# Adafruit_TRRS_Trinkey.net
KiCad netlist of a schematic drawn in EAGLE
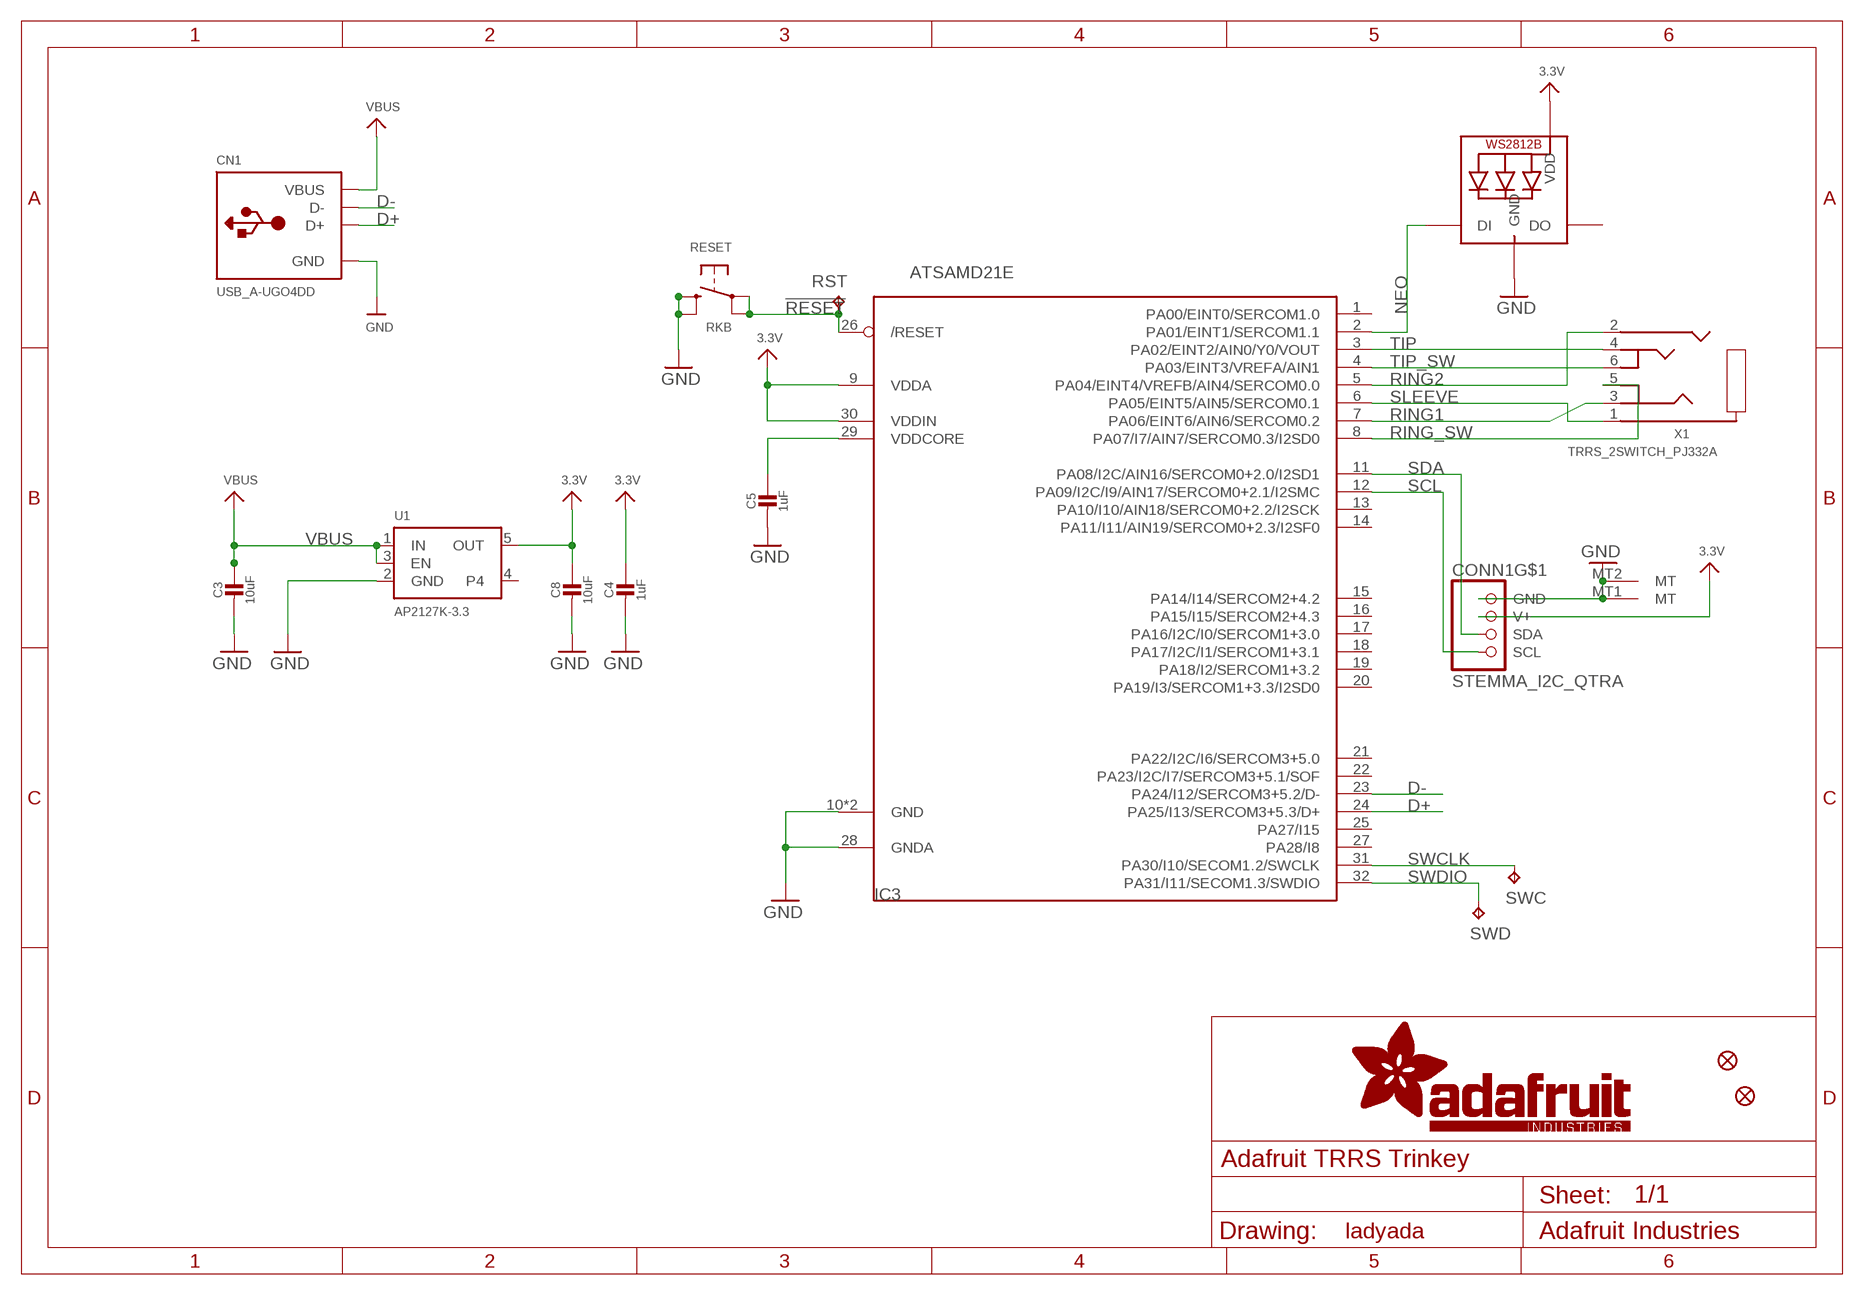
[diagram p0: schematic, sheet 1]

(export (version "E")
  (design (tool "Eeschema 10.0.6"))
  (components
    (comp (ref "C3")
      (value "10uF")
      (footprint "eagle-import:0805-NO")
      (libsource (lib "eagle-import") (part "CAP_CERAMIC0805-NOOUTLINE"))
    )
    (comp (ref "C4")
      (value "1uF")
      (footprint "eagle-import:0603-NO")
      (libsource (lib "eagle-import") (part "CAP_CERAMIC0603_NO"))
    )
    (comp (ref "C5")
      (value "1uF")
      (footprint "eagle-import:0603-NO")
      (libsource (lib "eagle-import") (part "CAP_CERAMIC0603_NO"))
    )
    (comp (ref "C8")
      (value "10uF")
      (footprint "eagle-import:0805-NO")
      (libsource (lib "eagle-import") (part "CAP_CERAMIC0805-NOOUTLINE"))
    )
    (comp (ref "CN1")
      (value "USB_A-UGO4DD")
      (footprint "eagle-import:USB_A-UGO4DD")
      (libsource (lib "eagle-import") (part "USB_TYPEA_UG04DD"))
    )
    (comp (ref "CONN1")
      (value "STEMMA_I2C_QTRA")
      (footprint "eagle-import:JST_SH4_RA")
      (libsource (lib "eagle-import") (part "STEMMA_I2C_QTRA"))
    )
    (comp (ref "FID1")
      (value "FIDUCIAL_0.5MM")
      (footprint "eagle-import:FIDUCIAL_0.5MM")
      (libsource (lib "eagle-import") (part "FIDUCIAL_0.5MM"))
    )
    (comp (ref "FID2")
      (value "FIDUCIAL_0.5MM")
      (footprint "eagle-import:FIDUCIAL_0.5MM")
      (libsource (lib "eagle-import") (part "FIDUCIAL_0.5MM"))
    )
    (comp (ref "IC3")
      (value "ATSAMD21E")
      (footprint "eagle-import:QFN32_5MM")
      (libsource (lib "eagle-import") (part "ATSAMD21E"))
    )
    (comp (ref "LED1")
      (value "WS2812B_SK6805_1515")
      (footprint "eagle-import:SK6805_1515")
      (libsource (lib "eagle-import") (part "WS2812B_SK6805_1515"))
    )
    (comp (ref "RESET")
      (value "RKB")
      (footprint "eagle-import:BTN_RKB2_4.6X2.8")
      (libsource (lib "eagle-import") (part "SWITCH_TACT_SMT_RKB2"))
    )
    (comp (ref "RST")
      (value "TPTP16R")
      (footprint "eagle-import:TP16R")
      (libsource (lib "eagle-import") (part "TPTP16R"))
    )
    (comp (ref "SWC")
      (value "TPTP15R")
      (footprint "eagle-import:TP15R")
      (libsource (lib "eagle-import") (part "TPTP15R"))
    )
    (comp (ref "SWD")
      (value "TPTP16R")
      (footprint "eagle-import:TP16R")
      (libsource (lib "eagle-import") (part "TPTP16R"))
    )
    (comp (ref "U1")
      (value "AP2127K-3.3")
      (footprint "eagle-import:SOT23-5")
      (fields (field (name "JLC_ROTATION") "0"))
      (libsource (lib "eagle-import") (part "VREG_SOT23-5"))
    )
    (comp (ref "X1")
      (value "TRRS_2SWITCH_PJ332A")
      (footprint "eagle-import:PJ-332A")
      (libsource (lib "eagle-import") (part "TRRS_2SWITCH_PJ332A"))
    )
  )
  (nets
    (net (code "1") (name "/D+") (class "Default")
      (node (ref "CN1") (pin "D+") (pinfunction "D+_D+") (pintype "bidirectional"))
      (node (ref "IC3") (pin "24") (pinfunction "PA25/I13/SERCOM3+5.3/D+_24") (pintype "bidirectional"))
    )
    (net (code "2") (name "/D-") (class "Default")
      (node (ref "CN1") (pin "D-") (pinfunction "D-_D-") (pintype "bidirectional"))
      (node (ref "IC3") (pin "23") (pinfunction "PA24/I12/SERCOM3+5.2/D-_23") (pintype "bidirectional"))
    )
    (net (code "3") (name "/NEO") (class "Default")
      (node (ref "IC3") (pin "2") (pinfunction "PA01/EINT1/SERCOM1.1_2") (pintype "bidirectional"))
      (node (ref "LED1") (pin "1") (pinfunction "DI_1") (pintype "input"))
    )
    (net (code "4") (name "/RING1") (class "Default")
      (node (ref "IC3") (pin "7") (pinfunction "PA06/EINT6/AIN6/SERCOM0.2_7") (pintype "bidirectional"))
      (node (ref "X1") (pin "3") (pinfunction "RING2_3") (pintype "passive"))
    )
    (net (code "5") (name "/RING2") (class "Default")
      (node (ref "IC3") (pin "5") (pinfunction "PA04/EINT4/VREFB/AIN4/SERCOM0.0_5") (pintype "bidirectional"))
      (node (ref "X1") (pin "2") (pinfunction "RING1_2") (pintype "passive"))
    )
    (net (code "6") (name "/RING_SW") (class "Default")
      (node (ref "IC3") (pin "8") (pinfunction "PA07/I7/AIN7/SERCOM0.3/I2SD0_8") (pintype "bidirectional"))
      (node (ref "X1") (pin "5") (pinfunction "R2_SW_5") (pintype "passive"))
    )
    (net (code "7") (name "/SCL") (class "Default")
      (node (ref "CONN1") (pin "4") (pinfunction "SCL_4") (pintype "passive"))
      (node (ref "IC3") (pin "12") (pinfunction "PA09/I2C/I9/AIN17/SERCOM0+2.1/I2SMC_12") (pintype "bidirectional"))
    )
    (net (code "8") (name "/SDA") (class "Default")
      (node (ref "CONN1") (pin "3") (pinfunction "SDA_3") (pintype "passive"))
      (node (ref "IC3") (pin "11") (pinfunction "PA08/I2C/AIN16/SERCOM0+2.0/I2SD1_11") (pintype "bidirectional"))
    )
    (net (code "9") (name "/SLEEVE") (class "Default")
      (node (ref "IC3") (pin "6") (pinfunction "PA05/EINT5/AIN5/SERCOM0.1_6") (pintype "bidirectional"))
      (node (ref "X1") (pin "1") (pinfunction "RING_1") (pintype "passive"))
    )
    (net (code "10") (name "/SWCLK") (class "Default")
      (node (ref "IC3") (pin "31") (pinfunction "PA30/I10/SECOM1.2/SWCLK_31") (pintype "bidirectional"))
      (node (ref "SWC") (pin "TP") (pinfunction "TP_TP") (pintype "input"))
    )
    (net (code "11") (name "/SWDIO") (class "Default")
      (node (ref "IC3") (pin "32") (pinfunction "PA31/I11/SECOM1.3/SWDIO_32") (pintype "bidirectional"))
      (node (ref "SWD") (pin "TP") (pinfunction "TP_TP") (pintype "input"))
    )
    (net (code "12") (name "/TIP") (class "Default")
      (node (ref "IC3") (pin "3") (pinfunction "PA02/EINT2/AIN0/Y0/VOUT_3") (pintype "bidirectional"))
      (node (ref "X1") (pin "4") (pinfunction "TIP_4") (pintype "passive"))
    )
    (net (code "13") (name "/TIP_SW") (class "Default")
      (node (ref "IC3") (pin "4") (pinfunction "PA03/EINT3/VREFA/AIN1_4") (pintype "bidirectional"))
      (node (ref "X1") (pin "6") (pinfunction "TIP_SW_6") (pintype "passive"))
    )
    (net (code "14") (name "/~{RESET}") (class "Default")
      (node (ref "IC3") (pin "26") (pinfunction "/RESET_26") (pintype "bidirectional"))
      (node (ref "RESET") (pin "A") (pinfunction "P_A") (pintype "passive"))
      (node (ref "RESET") (pin "A'") (pinfunction "P1_A'") (pintype "passive"))
      (node (ref "RST") (pin "TP") (pinfunction "TP_TP") (pintype "input"))
    )
    (net (code "15") (name "3.3V") (class "Default")
      (node (ref "C4") (pin "1") (pinfunction "1_1") (pintype "passive"))
      (node (ref "C8") (pin "1") (pinfunction "1_1") (pintype "passive"))
      (node (ref "CONN1") (pin "2") (pinfunction "V+_2") (pintype "passive"))
      (node (ref "IC3") (pin "30") (pinfunction "VDDIN_30") (pintype "power_in"))
      (node (ref "IC3") (pin "9") (pinfunction "VDDA_9") (pintype "power_in"))
      (node (ref "LED1") (pin "2") (pinfunction "VDD_2") (pintype "power_in"))
      (node (ref "U1") (pin "5") (pinfunction "OUT_5") (pintype "power_in"))
    )
    (net (code "16") (name "GND") (class "Default")
      (node (ref "C3") (pin "2") (pinfunction "2_2") (pintype "passive"))
      (node (ref "C4") (pin "2") (pinfunction "2_2") (pintype "passive"))
      (node (ref "C5") (pin "2") (pinfunction "2_2") (pintype "passive"))
      (node (ref "C8") (pin "2") (pinfunction "2_2") (pintype "passive"))
      (node (ref "CN1") (pin "GND") (pinfunction "GND_GND") (pintype "power_in"))
      (node (ref "CONN1") (pin "1") (pinfunction "GND_1") (pintype "passive"))
      (node (ref "CONN1") (pin "MT1") (pinfunction "MT_MT1") (pintype "bidirectional"))
      (node (ref "CONN1") (pin "MT2") (pinfunction "MT_MT2") (pintype "bidirectional"))
      (node (ref "IC3") (pin "10") (pinfunction "GND_10") (pintype "power_in"))
      (node (ref "IC3") (pin "28") (pinfunction "GNDA_28") (pintype "power_in"))
      (node (ref "IC3") (pin "33") (pinfunction "GND_33") (pintype "power_in"))
      (node (ref "LED1") (pin "4") (pinfunction "GND_4") (pintype "power_in"))
      (node (ref "RESET") (pin "B") (pinfunction "S_B") (pintype "passive"))
      (node (ref "RESET") (pin "B'") (pinfunction "S1_B'") (pintype "passive"))
      (node (ref "U1") (pin "2") (pinfunction "GND_2") (pintype "power_in"))
    )
    (net (code "17") (name "Net-(IC3-VDDCORE)") (class "Default")
      (node (ref "C5") (pin "1") (pinfunction "1_1") (pintype "passive"))
      (node (ref "IC3") (pin "29") (pinfunction "VDDCORE_29") (pintype "power_in"))
    )
    (net (code "18") (name "VBUS") (class "Default")
      (node (ref "C3") (pin "1") (pinfunction "1_1") (pintype "passive"))
      (node (ref "CN1") (pin "VBUS") (pinfunction "VBUS_VBUS") (pintype "power_in"))
      (node (ref "U1") (pin "1") (pinfunction "IN_1") (pintype "power_in"))
      (node (ref "U1") (pin "3") (pinfunction "EN_3") (pintype "input"))
    )
    (net (code "19") (name "unconnected-(IC3-PA00{slash}EINT0{slash}SERCOM1.0-Pad1)") (class "Default")
      (node (ref "IC3") (pin "1") (pinfunction "PA00/EINT0/SERCOM1.0_1") (pintype "bidirectional"))
    )
    (net (code "20") (name "unconnected-(IC3-PA10{slash}I10{slash}AIN18{slash}SERCOM0+2.2{slash}I2SCK-Pad13)") (class "Default")
      (node (ref "IC3") (pin "13") (pinfunction "PA10/I10/AIN18/SERCOM0+2.2/I2SCK_13") (pintype "bidirectional"))
    )
    (net (code "21") (name "unconnected-(IC3-PA11{slash}I11{slash}AIN19{slash}SERCOM0+2.3{slash}I2SF0-Pad14)") (class "Default")
      (node (ref "IC3") (pin "14") (pinfunction "PA11/I11/AIN19/SERCOM0+2.3/I2SF0_14") (pintype "bidirectional"))
    )
    (net (code "22") (name "unconnected-(IC3-PA14{slash}I14{slash}SERCOM2+4.2-Pad15)") (class "Default")
      (node (ref "IC3") (pin "15") (pinfunction "PA14/I14/SERCOM2+4.2_15") (pintype "bidirectional"))
    )
    (net (code "23") (name "unconnected-(IC3-PA15{slash}I15{slash}SERCOM2+4.3-Pad16)") (class "Default")
      (node (ref "IC3") (pin "16") (pinfunction "PA15/I15/SERCOM2+4.3_16") (pintype "bidirectional"))
    )
    (net (code "24") (name "unconnected-(IC3-PA16{slash}I2C{slash}I0{slash}SERCOM1+3.0-Pad17)") (class "Default")
      (node (ref "IC3") (pin "17") (pinfunction "PA16/I2C/I0/SERCOM1+3.0_17") (pintype "bidirectional"))
    )
    (net (code "25") (name "unconnected-(IC3-PA17{slash}I2C{slash}I1{slash}SERCOM1+3.1-Pad18)") (class "Default")
      (node (ref "IC3") (pin "18") (pinfunction "PA17/I2C/I1/SERCOM1+3.1_18") (pintype "bidirectional"))
    )
    (net (code "26") (name "unconnected-(IC3-PA18{slash}I2{slash}SERCOM1+3.2-Pad19)") (class "Default")
      (node (ref "IC3") (pin "19") (pinfunction "PA18/I2/SERCOM1+3.2_19") (pintype "bidirectional"))
    )
    (net (code "27") (name "unconnected-(IC3-PA19{slash}I3{slash}SERCOM1+3.3{slash}I2SD0-Pad20)") (class "Default")
      (node (ref "IC3") (pin "20") (pinfunction "PA19/I3/SERCOM1+3.3/I2SD0_20") (pintype "bidirectional"))
    )
    (net (code "28") (name "unconnected-(IC3-PA22{slash}I2C{slash}I6{slash}SERCOM3+5.0-Pad21)") (class "Default")
      (node (ref "IC3") (pin "21") (pinfunction "PA22/I2C/I6/SERCOM3+5.0_21") (pintype "bidirectional"))
    )
    (net (code "29") (name "unconnected-(IC3-PA23{slash}I2C{slash}I7{slash}SERCOM3+5.1{slash}SOF-Pad22)") (class "Default")
      (node (ref "IC3") (pin "22") (pinfunction "PA23/I2C/I7/SERCOM3+5.1/SOF_22") (pintype "bidirectional"))
    )
    (net (code "30") (name "unconnected-(IC3-PA27{slash}I15-Pad25)") (class "Default")
      (node (ref "IC3") (pin "25") (pinfunction "PA27/I15_25") (pintype "bidirectional"))
    )
    (net (code "31") (name "unconnected-(IC3-PA28{slash}I8-Pad27)") (class "Default")
      (node (ref "IC3") (pin "27") (pinfunction "PA28/I8_27") (pintype "bidirectional"))
    )
    (net (code "32") (name "unconnected-(LED1-DO-Pad3)") (class "Default")
      (node (ref "LED1") (pin "3") (pinfunction "DO_3") (pintype "output"))
    )
    (net (code "33") (name "unconnected-(U1-P4-Pad4)") (class "Default")
      (node (ref "U1") (pin "4") (pinfunction "P4_4") (pintype "bidirectional"))
    )
  )
)
